# Sheet_1_2022-03-10.net
KiCad netlist of a schematic drawn in Altium Designer
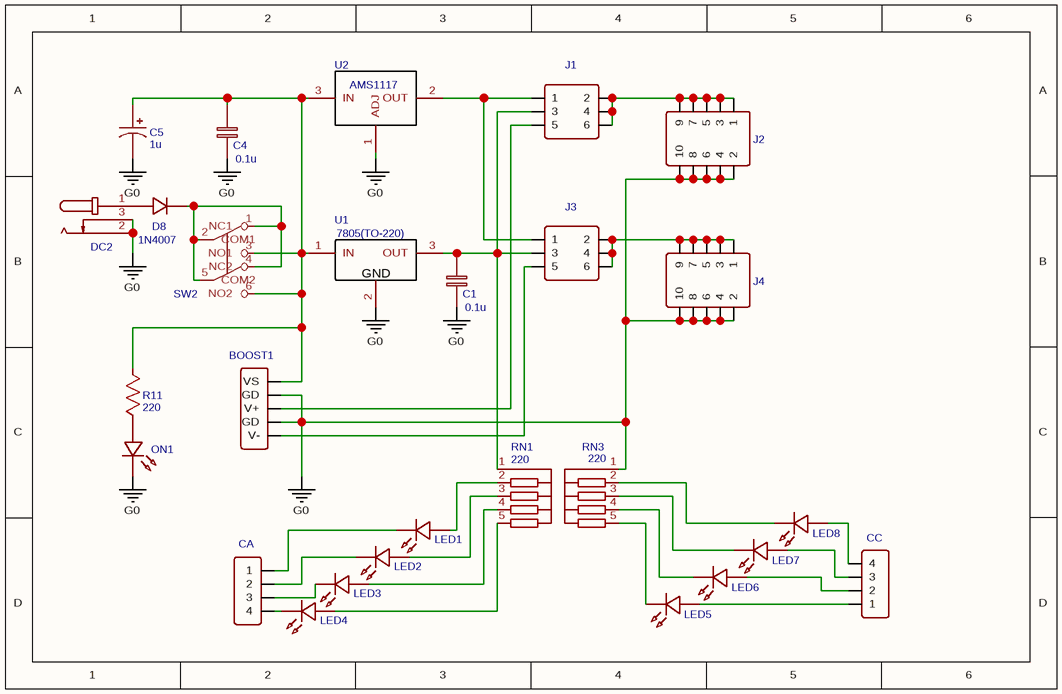
[diagram p0: Sheet_1_2022-03-10.schdoc]

(export (version "E")
  (design (tool "Eeschema 10.0.6"))
  (components
    (comp (ref "BOOST1")
      (value "HDR-F-2.54_1x5")
      (fields (field (name "BOM_SUPPLIER PART") "C50950") (field (name "CONTRIBUTOR") "LCEDA_Lib"))
      (libsource (lib "altium-import") (part "root_2_HDR-F-2.54_1x5_"))
    )
    (comp (ref "C1")
      (value "0.1u")
      (fields (field (name "CONTRIBUTOR") "LCEDA_Lib"))
      (libsource (lib "altium-import") (part "root_1_0.1u_"))
    )
    (comp (ref "C4")
      (value "0.1u")
      (fields (field (name "CONTRIBUTOR") "LCEDA_Lib"))
      (libsource (lib "altium-import") (part "root_1_0.1u_"))
    )
    (comp (ref "C5")
      (value "1u")
      (fields (field (name "CONTRIBUTOR") "LCEDA_Lib"))
      (libsource (lib "altium-import") (part "root_3_1u_"))
    )
    (comp (ref "CA")
      (value "HDR-F-2.54_1x4")
      (fields (field (name "BOM_SUPPLIER PART") "C225501") (field (name "CONTRIBUTOR") "LCEDA_Lib"))
      (libsource (lib "altium-import") (part "root_2_HDR-F-2.54_1x4_"))
    )
    (comp (ref "CC")
      (value "HDR-F-2.54_1x4")
      (fields (field (name "BOM_SUPPLIER PART") "C225501") (field (name "CONTRIBUTOR") "LCEDA_Lib"))
      (libsource (lib "altium-import") (part "root_0_HDR-F-2.54_1x4_"))
    )
    (comp (ref "D8")
      (value "1N4007")
      (fields (field (name "BOM_SUPPLIER PART") "C106903") (field (name "CONTRIBUTOR") "LCEDA_Lib"))
      (libsource (lib "altium-import") (part "root_0_1N4007_"))
    )
    (comp (ref "DC2")
      (value "DC-072-165A")
      (fields (field (name "BOM_SUPPLIER PART") "C129003"))
      (libsource (lib "altium-import") (part "root_0_DC-072-165A_"))
    )
    (comp (ref "J1")
      (value "HDR-M-2.54_2x3")
      (fields (field (name "BOM_SUPPLIER PART") "C65114") (field (name "CONTRIBUTOR") "LCEDA_Lib"))
      (libsource (lib "altium-import") (part "root_0_HDR-M-2.54_2x3_"))
    )
    (comp (ref "J2")
      (value "HDR-M-2.54_2x5")
      (fields (field (name "BOM_SUPPLIER PART") "C178292") (field (name "CONTRIBUTOR") "LCEDA_Lib"))
      (libsource (lib "altium-import") (part "root_3_HDR-M-2.54_2x5_"))
    )
    (comp (ref "J3")
      (value "HDR-M-2.54_2x3")
      (fields (field (name "BOM_SUPPLIER PART") "C65114") (field (name "CONTRIBUTOR") "LCEDA_Lib"))
      (libsource (lib "altium-import") (part "root_0_HDR-M-2.54_2x3_"))
    )
    (comp (ref "J4")
      (value "HDR-M-2.54_2x5")
      (fields (field (name "BOM_SUPPLIER PART") "C178292") (field (name "CONTRIBUTOR") "LCEDA_Lib"))
      (libsource (lib "altium-import") (part "root_3_HDR-M-2.54_2x5_"))
    )
    (comp (ref "LED1")
      (value "LED-TH-3mm_R")
      (fields
        (field (name "BOM_MANUFACTURER PART") "204-10SDRD/S530-A3-L")
        (field (name "BOM_SUPPLIER PART") "C84774")
        (field (name "CONTRIBUTOR") "LCEDA_Lib")
      )
      (libsource (lib "altium-import") (part "root_2_LED-TH-3mm_R_"))
    )
    (comp (ref "LED2")
      (value "LED-TH-3mm_R")
      (fields
        (field (name "BOM_MANUFACTURER PART") "204-10SDRD/S530-A3-L")
        (field (name "BOM_SUPPLIER PART") "C84774")
        (field (name "CONTRIBUTOR") "LCEDA_Lib")
      )
      (libsource (lib "altium-import") (part "root_2_LED-TH-3mm_R_"))
    )
    (comp (ref "LED3")
      (value "LED-TH-3mm_R")
      (fields
        (field (name "BOM_MANUFACTURER PART") "204-10SDRD/S530-A3-L")
        (field (name "BOM_SUPPLIER PART") "C84774")
        (field (name "CONTRIBUTOR") "LCEDA_Lib")
      )
      (libsource (lib "altium-import") (part "root_2_LED-TH-3mm_R_"))
    )
    (comp (ref "LED4")
      (value "LED-TH-3mm_R")
      (fields
        (field (name "BOM_MANUFACTURER PART") "204-10SDRD/S530-A3-L")
        (field (name "BOM_SUPPLIER PART") "C84774")
        (field (name "CONTRIBUTOR") "LCEDA_Lib")
      )
      (libsource (lib "altium-import") (part "root_2_LED-TH-3mm_R_"))
    )
    (comp (ref "LED5")
      (value "LED-TH-3mm_R")
      (fields
        (field (name "BOM_MANUFACTURER PART") "204-10SDRD/S530-A3-L")
        (field (name "BOM_SUPPLIER PART") "C84774")
        (field (name "CONTRIBUTOR") "LCEDA_Lib")
      )
      (libsource (lib "altium-import") (part "root_2_LED-TH-3mm_R_"))
    )
    (comp (ref "LED6")
      (value "LED-TH-3mm_R")
      (fields
        (field (name "BOM_MANUFACTURER PART") "204-10SDRD/S530-A3-L")
        (field (name "BOM_SUPPLIER PART") "C84774")
        (field (name "CONTRIBUTOR") "LCEDA_Lib")
      )
      (libsource (lib "altium-import") (part "root_2_LED-TH-3mm_R_"))
    )
    (comp (ref "LED7")
      (value "LED-TH-3mm_R")
      (fields
        (field (name "BOM_MANUFACTURER PART") "204-10SDRD/S530-A3-L")
        (field (name "BOM_SUPPLIER PART") "C84774")
        (field (name "CONTRIBUTOR") "LCEDA_Lib")
      )
      (libsource (lib "altium-import") (part "root_2_LED-TH-3mm_R_"))
    )
    (comp (ref "LED8")
      (value "LED-TH-3mm_R")
      (fields
        (field (name "BOM_MANUFACTURER PART") "204-10SDRD/S530-A3-L")
        (field (name "BOM_SUPPLIER PART") "C84774")
        (field (name "CONTRIBUTOR") "LCEDA_Lib")
      )
      (libsource (lib "altium-import") (part "root_2_LED-TH-3mm_R_"))
    )
    (comp (ref "ON1")
      (value "LED-TH-3mm_B")
      (fields
        (field (name "BOM_MANUFACTURER PART") "204-10SUBC/S400-A4")
        (field (name "BOM_SUPPLIER PART") "C86881")
        (field (name "CONTRIBUTOR") "LCEDA_Lib")
      )
      (libsource (lib "altium-import") (part "root_3_LED-TH-3mm_B_"))
    )
    (comp (ref "R11")
      (value "220")
      (fields (field (name "CONTRIBUTOR") "LCEDA_Lib"))
      (libsource (lib "") (part "root_1_220__1"))
    )
    (comp (ref "RN1")
      (value "220")
      (fields
        (field (name "BOM_SUPPLIER PART") "C353598")
        (field (name "BOM_MANUFACTURER PART") "RAA05472G")
        (field (name "CONTRIBUTOR") "LCSC")
      )
      (libsource (lib "altium-import") (part "root_3_220_"))
    )
    (comp (ref "RN3")
      (value "220")
      (fields
        (field (name "BOM_SUPPLIER PART") "C353598")
        (field (name "BOM_MANUFACTURER PART") "RAA05472G")
        (field (name "CONTRIBUTOR") "LCSC")
      )
      (libsource (lib "altium-import") (part "root_1_220_"))
    )
    (comp (ref "SW2")
      (value "SW_PUSH_DPDT")
      (fields (field (name "CONTRIBUTOR") "DangerousPrototype"))
      (libsource (lib "altium-import") (part "root_0_SW_PUSH_DPDT_"))
    )
    (comp (ref "U1")
      (value "7805(TO-220)")
      (fields
        (field (name "BOM_MANUFACTURER PART") "L7805CV-DG")
        (field (name "BOM_SUPPLIER PART") "C3795")
        (field (name "CONTRIBUTOR") "LCEDA_Lib")
      )
      (libsource (lib "altium-import") (part "root_0_7805(TO-220)_"))
    )
    (comp (ref "U2")
      (value "AMS1117")
      (fields (field (name "CONTRIBUTOR") "GerryChen"))
      (libsource (lib "altium-import") (part "root_0_AMS1117_"))
    )
  )
  (nets
    (net (code "1") (name "G0") (class "Default")
      (node (ref "BOOST1") (pin "2") (pinfunction "GD_2") (pintype "passive"))
      (node (ref "BOOST1") (pin "4") (pinfunction "GD_4") (pintype "passive"))
      (node (ref "C1") (pin "1") (pinfunction "1_1") (pintype "passive"))
      (node (ref "C4") (pin "1") (pinfunction "1_1") (pintype "passive"))
      (node (ref "C5") (pin "2") (pinfunction "2_2") (pintype "passive"))
      (node (ref "DC2") (pin "2") (pinfunction "2_2") (pintype "passive"))
      (node (ref "DC2") (pin "3") (pinfunction "3_3") (pintype "passive"))
      (node (ref "J2") (pin "10") (pinfunction "10_10") (pintype "passive"))
      (node (ref "J2") (pin "2") (pinfunction "2_2") (pintype "passive"))
      (node (ref "J2") (pin "4") (pinfunction "4_4") (pintype "passive"))
      (node (ref "J2") (pin "6") (pinfunction "6_6") (pintype "passive"))
      (node (ref "J2") (pin "8") (pinfunction "8_8") (pintype "passive"))
      (node (ref "J4") (pin "10") (pinfunction "10_10") (pintype "passive"))
      (node (ref "J4") (pin "2") (pinfunction "2_2") (pintype "passive"))
      (node (ref "J4") (pin "4") (pinfunction "4_4") (pintype "passive"))
      (node (ref "J4") (pin "6") (pinfunction "6_6") (pintype "passive"))
      (node (ref "J4") (pin "8") (pinfunction "8_8") (pintype "passive"))
      (node (ref "ON1") (pin "2") (pinfunction "2_2") (pintype "passive"))
      (node (ref "RN3") (pin "1") (pinfunction "1_1") (pintype "passive"))
      (node (ref "U1") (pin "2") (pinfunction "GND_2") (pintype "passive"))
      (node (ref "U2") (pin "1") (pinfunction "ADJ_1") (pintype "passive"))
    )
    (net (code "2") (name "Net-(BOOST1-V+)") (class "Default")
      (node (ref "BOOST1") (pin "3") (pinfunction "V+_3") (pintype "passive"))
      (node (ref "J1") (pin "5") (pinfunction "5_5") (pintype "passive"))
    )
    (net (code "3") (name "Net-(BOOST1-V-)") (class "Default")
      (node (ref "BOOST1") (pin "5") (pinfunction "V-_5") (pintype "passive"))
      (node (ref "J3") (pin "5") (pinfunction "5_5") (pintype "passive"))
    )
    (net (code "4") (name "Net-(BOOST1-VS)") (class "Default")
      (node (ref "BOOST1") (pin "1") (pinfunction "VS_1") (pintype "passive"))
      (node (ref "C4") (pin "2") (pinfunction "2_2") (pintype "passive"))
      (node (ref "C5") (pin "1") (pinfunction "1_1") (pintype "passive"))
      (node (ref "R11") (pin "2") (pinfunction "2_2") (pintype "passive"))
      (node (ref "SW2") (pin "3") (pinfunction "NO1_3") (pintype "passive"))
      (node (ref "SW2") (pin "6") (pinfunction "NO2_6") (pintype "passive"))
      (node (ref "U1") (pin "1") (pinfunction "IN_1") (pintype "passive"))
      (node (ref "U2") (pin "3") (pinfunction "IN_3") (pintype "passive"))
    )
    (net (code "5") (name "Net-(CA-Pad1)") (class "Default")
      (node (ref "CA") (pin "1") (pinfunction "1_1") (pintype "passive"))
      (node (ref "LED1") (pin "2") (pinfunction "2_2") (pintype "passive"))
    )
    (net (code "6") (name "Net-(CA-Pad2)") (class "Default")
      (node (ref "CA") (pin "2") (pinfunction "2_2") (pintype "passive"))
      (node (ref "LED2") (pin "2") (pinfunction "2_2") (pintype "passive"))
    )
    (net (code "7") (name "Net-(CA-Pad3)") (class "Default")
      (node (ref "CA") (pin "3") (pinfunction "3_3") (pintype "passive"))
      (node (ref "LED3") (pin "2") (pinfunction "2_2") (pintype "passive"))
    )
    (net (code "8") (name "Net-(CA-Pad4)") (class "Default")
      (node (ref "CA") (pin "4") (pinfunction "4_4") (pintype "passive"))
      (node (ref "LED4") (pin "2") (pinfunction "2_2") (pintype "passive"))
    )
    (net (code "9") (name "Net-(CC-Pad1)") (class "Default")
      (node (ref "CC") (pin "1") (pinfunction "1_1") (pintype "passive"))
      (node (ref "LED5") (pin "1") (pinfunction "1_1") (pintype "passive"))
    )
    (net (code "10") (name "Net-(CC-Pad2)") (class "Default")
      (node (ref "CC") (pin "2") (pinfunction "2_2") (pintype "passive"))
      (node (ref "LED6") (pin "1") (pinfunction "1_1") (pintype "passive"))
    )
    (net (code "11") (name "Net-(CC-Pad3)") (class "Default")
      (node (ref "CC") (pin "3") (pinfunction "3_3") (pintype "passive"))
      (node (ref "LED7") (pin "1") (pinfunction "1_1") (pintype "passive"))
    )
    (net (code "12") (name "Net-(CC-Pad4)") (class "Default")
      (node (ref "CC") (pin "4") (pinfunction "4_4") (pintype "passive"))
      (node (ref "LED8") (pin "1") (pinfunction "1_1") (pintype "passive"))
    )
    (net (code "13") (name "Net-(D8-Pad2)") (class "Default")
      (node (ref "D8") (pin "2") (pinfunction "2_2") (pintype "passive"))
      (node (ref "DC2") (pin "1") (pinfunction "1_1") (pintype "passive"))
    )
    (net (code "14") (name "Net-(J1-Pad2)") (class "Default")
      (node (ref "J1") (pin "2") (pinfunction "2_2") (pintype "passive"))
      (node (ref "J1") (pin "4") (pinfunction "4_4") (pintype "passive"))
      (node (ref "J1") (pin "6") (pinfunction "6_6") (pintype "passive"))
      (node (ref "J2") (pin "1") (pinfunction "1_1") (pintype "passive"))
      (node (ref "J2") (pin "3") (pinfunction "3_3") (pintype "passive"))
      (node (ref "J2") (pin "5") (pinfunction "5_5") (pintype "passive"))
      (node (ref "J2") (pin "7") (pinfunction "7_7") (pintype "passive"))
      (node (ref "J2") (pin "9") (pinfunction "9_9") (pintype "passive"))
    )
    (net (code "15") (name "Net-(J3-Pad2)") (class "Default")
      (node (ref "J3") (pin "2") (pinfunction "2_2") (pintype "passive"))
      (node (ref "J3") (pin "4") (pinfunction "4_4") (pintype "passive"))
      (node (ref "J3") (pin "6") (pinfunction "6_6") (pintype "passive"))
      (node (ref "J4") (pin "1") (pinfunction "1_1") (pintype "passive"))
      (node (ref "J4") (pin "3") (pinfunction "3_3") (pintype "passive"))
      (node (ref "J4") (pin "5") (pinfunction "5_5") (pintype "passive"))
      (node (ref "J4") (pin "7") (pinfunction "7_7") (pintype "passive"))
      (node (ref "J4") (pin "9") (pinfunction "9_9") (pintype "passive"))
    )
    (net (code "16") (name "Net-(LED1-Pad1)") (class "Default")
      (node (ref "LED1") (pin "1") (pinfunction "1_1") (pintype "passive"))
      (node (ref "RN1") (pin "2") (pinfunction "2_2") (pintype "passive"))
    )
    (net (code "17") (name "Net-(LED2-Pad1)") (class "Default")
      (node (ref "LED2") (pin "1") (pinfunction "1_1") (pintype "passive"))
      (node (ref "RN1") (pin "3") (pinfunction "3_3") (pintype "passive"))
    )
    (net (code "18") (name "Net-(LED3-Pad1)") (class "Default")
      (node (ref "LED3") (pin "1") (pinfunction "1_1") (pintype "passive"))
      (node (ref "RN1") (pin "4") (pinfunction "4_4") (pintype "passive"))
    )
    (net (code "19") (name "Net-(LED4-Pad1)") (class "Default")
      (node (ref "LED4") (pin "1") (pinfunction "1_1") (pintype "passive"))
      (node (ref "RN1") (pin "5") (pinfunction "5_5") (pintype "passive"))
    )
    (net (code "20") (name "Net-(LED5-Pad2)") (class "Default")
      (node (ref "LED5") (pin "2") (pinfunction "2_2") (pintype "passive"))
      (node (ref "RN3") (pin "5") (pinfunction "5_5") (pintype "passive"))
    )
    (net (code "21") (name "Net-(LED6-Pad2)") (class "Default")
      (node (ref "LED6") (pin "2") (pinfunction "2_2") (pintype "passive"))
      (node (ref "RN3") (pin "4") (pinfunction "4_4") (pintype "passive"))
    )
    (net (code "22") (name "Net-(LED7-Pad2)") (class "Default")
      (node (ref "LED7") (pin "2") (pinfunction "2_2") (pintype "passive"))
      (node (ref "RN3") (pin "3") (pinfunction "3_3") (pintype "passive"))
    )
    (net (code "23") (name "Net-(LED8-Pad2)") (class "Default")
      (node (ref "LED8") (pin "2") (pinfunction "2_2") (pintype "passive"))
      (node (ref "RN3") (pin "2") (pinfunction "2_2") (pintype "passive"))
    )
    (net (code "24") (name "Net-(ON1-Pad1)") (class "Default")
      (node (ref "ON1") (pin "1") (pinfunction "1_1") (pintype "passive"))
      (node (ref "R11") (pin "1") (pinfunction "1_1") (pintype "passive"))
    )
    (net (code "25") (name "Net-(SW2-COM1)") (class "Default")
      (node (ref "D8") (pin "1") (pinfunction "1_1") (pintype "passive"))
      (node (ref "SW2") (pin "1") (pinfunction "NC1_1") (pintype "passive"))
      (node (ref "SW2") (pin "2") (pinfunction "COM1_2") (pintype "passive"))
      (node (ref "SW2") (pin "4") (pinfunction "NC2_4") (pintype "passive"))
      (node (ref "SW2") (pin "5") (pinfunction "COM2_5") (pintype "passive"))
    )
    (net (code "26") (name "Net-(U1-OUT)") (class "Default")
      (node (ref "C1") (pin "2") (pinfunction "2_2") (pintype "passive"))
      (node (ref "J1") (pin "3") (pinfunction "3_3") (pintype "passive"))
      (node (ref "J3") (pin "3") (pinfunction "3_3") (pintype "passive"))
      (node (ref "RN1") (pin "1") (pinfunction "1_1") (pintype "passive"))
      (node (ref "U1") (pin "3") (pinfunction "OUT_3") (pintype "passive"))
    )
    (net (code "27") (name "Net-(U2-OUT)") (class "Default")
      (node (ref "J1") (pin "1") (pinfunction "1_1") (pintype "passive"))
      (node (ref "J3") (pin "1") (pinfunction "1_1") (pintype "passive"))
      (node (ref "U2") (pin "2") (pinfunction "OUT_2") (pintype "passive"))
    )
  )
)
